# Sheet1.net
KiCad netlist of a schematic drawn in Altium Designer
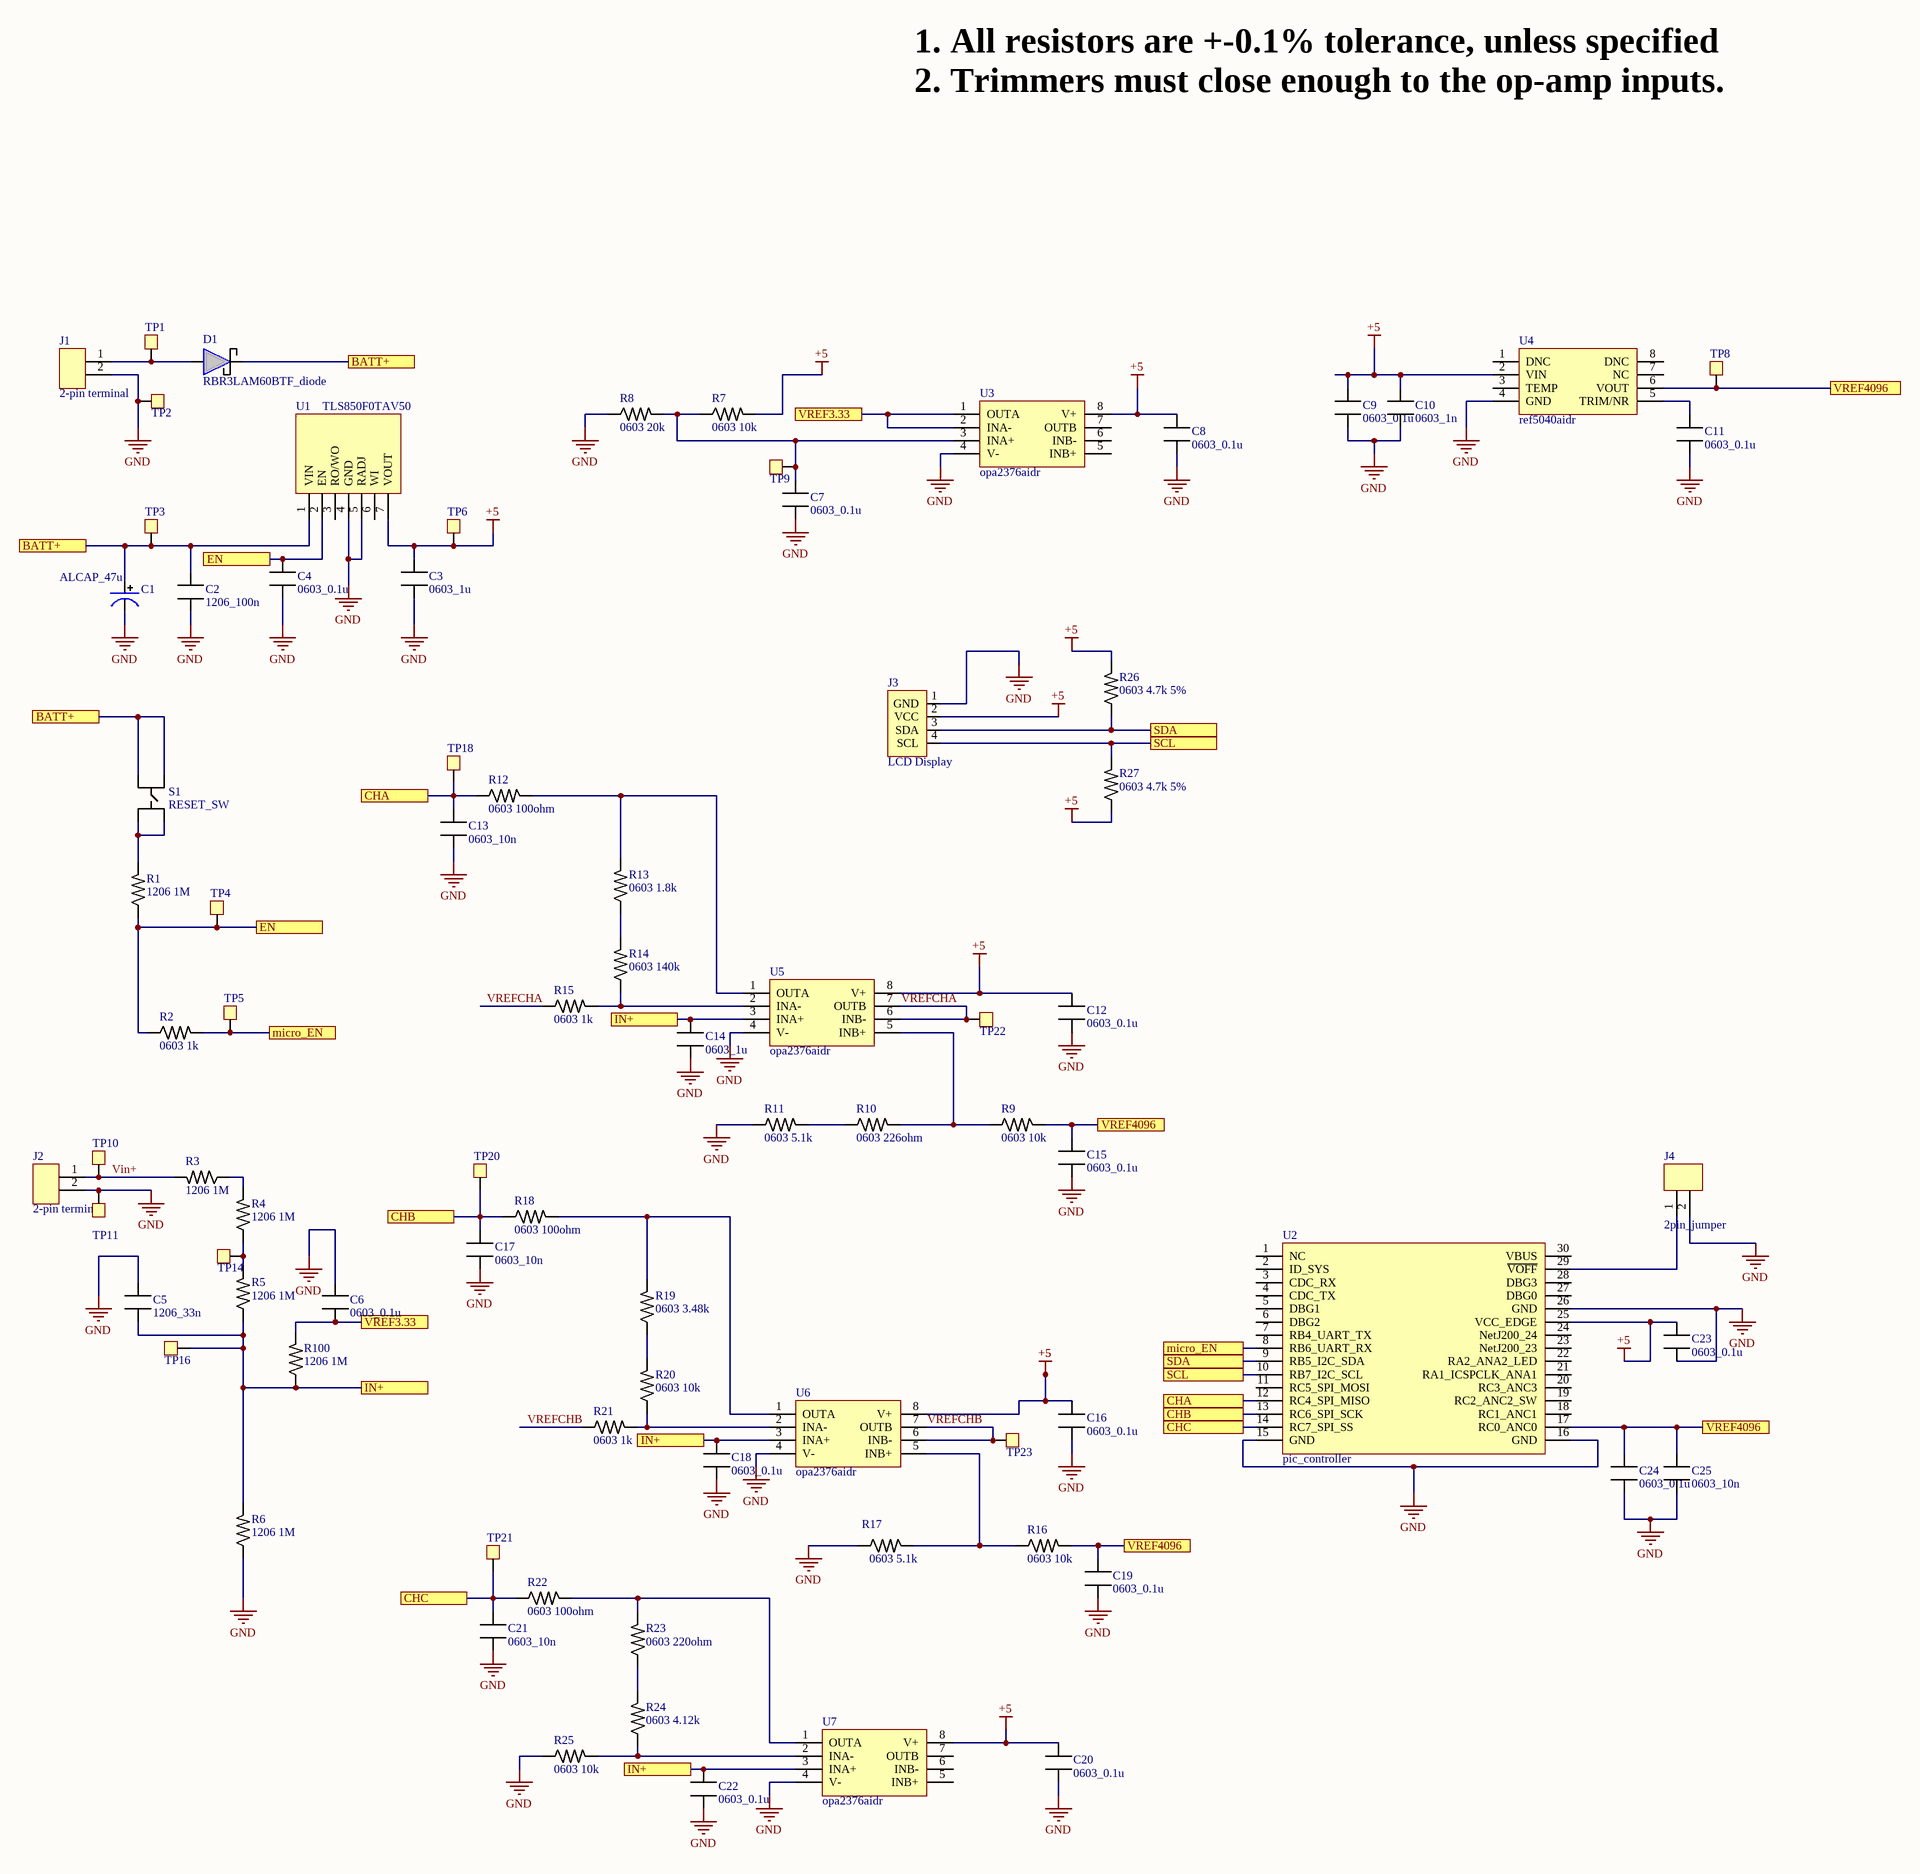
[diagram p0: Sheet1.SchDoc]

(export (version "E")
  (design (tool "Eeschema 10.0.6"))
  (components
    (comp (ref "C1")
      (value "ALCAP_47u")
      (footprint "47u_cap")
      (description "ALCAP")
      (libsource (lib "finallib") (part "ALCAP_47UF"))
    )
    (comp (ref "C2")
      (value "1206_100n")
      (footprint "CAPC3216X10M")
      (description "CAP_1206")
      (libsource (lib "finallib") (part "CAP_1206"))
    )
    (comp (ref "C3")
      (value "0603_1u")
      (footprint "CAP_0603")
      (description "CAP_0603")
      (libsource (lib "finallib") (part "CAP_0603"))
    )
    (comp (ref "C4")
      (value "0603_0.1u")
      (footprint "CAP_0603")
      (description "CAP_0603")
      (libsource (lib "finallib") (part "CAP_0603"))
    )
    (comp (ref "C5")
      (value "1206_33n")
      (footprint "CAPC3216X10M")
      (description "CAP_1206")
      (libsource (lib "finallib") (part "CAP_1206"))
    )
    (comp (ref "C6")
      (value "0603_0.1u")
      (footprint "CAP_0603")
      (description "CAP_0603")
      (libsource (lib "finallib") (part "CAP_0603"))
    )
    (comp (ref "C7")
      (value "0603_0.1u")
      (footprint "CAP_0603")
      (description "CAP_0603")
      (libsource (lib "finallib") (part "CAP_0603"))
    )
    (comp (ref "C8")
      (value "0603_0.1u")
      (footprint "CAP_0603")
      (description "CAP_0603")
      (libsource (lib "finallib") (part "CAP_0603"))
    )
    (comp (ref "C9")
      (value "0603_0.1u")
      (footprint "CAP_0603")
      (description "CAP_0603")
      (libsource (lib "finallib") (part "CAP_0603"))
    )
    (comp (ref "C10")
      (value "0603_1n")
      (footprint "CAP_0603")
      (description "CAP_0603")
      (libsource (lib "finallib") (part "CAP_0603"))
    )
    (comp (ref "C11")
      (value "0603_0.1u")
      (footprint "CAP_0603")
      (description "CAP_0603")
      (libsource (lib "finallib") (part "CAP_0603"))
    )
    (comp (ref "C12")
      (value "0603_0.1u")
      (footprint "CAP_0603")
      (description "CAP_0603")
      (libsource (lib "finallib") (part "CAP_0603"))
    )
    (comp (ref "C13")
      (value "0603_10n")
      (footprint "CAP_0603")
      (description "CAP_0603")
      (libsource (lib "finallib") (part "CAP_0603"))
    )
    (comp (ref "C14")
      (value "0603_1u")
      (footprint "CAP_0603")
      (description "CAP_0603")
      (libsource (lib "finallib") (part "CAP_0603"))
    )
    (comp (ref "C15")
      (value "0603_0.1u")
      (footprint "CAP_0603")
      (description "CAP_0603")
      (libsource (lib "finallib") (part "CAP_0603"))
    )
    (comp (ref "C16")
      (value "0603_0.1u")
      (footprint "CAP_0603")
      (description "CAP_0603")
      (libsource (lib "finallib") (part "CAP_0603"))
    )
    (comp (ref "C17")
      (value "0603_10n")
      (footprint "CAP_0603")
      (description "CAP_0603")
      (libsource (lib "finallib") (part "CAP_0603"))
    )
    (comp (ref "C18")
      (value "0603_0.1u")
      (footprint "CAP_0603")
      (description "CAP_0603")
      (libsource (lib "finallib") (part "CAP_0603"))
    )
    (comp (ref "C19")
      (value "0603_0.1u")
      (footprint "CAP_0603")
      (description "CAP_0603")
      (libsource (lib "finallib") (part "CAP_0603"))
    )
    (comp (ref "C20")
      (value "0603_0.1u")
      (footprint "CAP_0603")
      (description "CAP_0603")
      (libsource (lib "finallib") (part "CAP_0603"))
    )
    (comp (ref "C21")
      (value "0603_10n")
      (footprint "CAP_0603")
      (description "CAP_0603")
      (libsource (lib "finallib") (part "CAP_0603"))
    )
    (comp (ref "C22")
      (value "0603_0.1u")
      (footprint "CAP_0603")
      (description "CAP_0603")
      (libsource (lib "finallib") (part "CAP_0603"))
    )
    (comp (ref "C23")
      (value "0603_0.1u")
      (footprint "CAP_0603")
      (description "CAP_0603")
      (libsource (lib "finallib") (part "CAP_0603"))
    )
    (comp (ref "C24")
      (value "0603_0.1u")
      (footprint "CAP_0603")
      (description "CAP_0603")
      (libsource (lib "finallib") (part "CAP_0603"))
    )
    (comp (ref "C25")
      (value "0603_10n")
      (footprint "CAP_0603")
      (description "CAP_0603")
      (libsource (lib "finallib") (part "CAP_0603"))
    )
    (comp (ref "D1")
      (value "RBR3LAM60BTF_diode")
      (footprint "RBR3LAM60BTF_diode")
      (libsource (lib "finallib") (part "RBR3LAM60BTF_diode"))
    )
    (comp (ref "J1")
      (value "2-pin terminal")
      (footprint "2-pin terminal")
      (libsource (lib "finallib") (part "2-pin terminal"))
    )
    (comp (ref "J2")
      (value "2-pin terminal")
      (footprint "2-pin terminal")
      (libsource (lib "finallib") (part "2-pin terminal"))
    )
    (comp (ref "J3")
      (value "LCD Display")
      (footprint "LCD Display")
      (libsource (lib "finallib") (part "LCD Display"))
    )
    (comp (ref "J4")
      (value "2pin_jumper")
      (footprint "2pin_jumper")
      (libsource (lib "finallib") (part "2pin_jumper"))
    )
    (comp (ref "R1")
      (value "1206 1M")
      (footprint "RESC3216X10M")
      (description "RES_0603 1/8 W")
      (libsource (lib "finallib") (part "RES_0603"))
    )
    (comp (ref "R2")
      (value "0603 1k")
      (footprint "RES_0603")
      (description "RES_0603 1/8 W")
      (libsource (lib "finallib") (part "RES_0603"))
    )
    (comp (ref "R3")
      (value "1206 1M")
      (footprint "RESC3216X10M")
      (libsource (lib "finallib") (part "RES_1206"))
    )
    (comp (ref "R4")
      (value "1206 1M")
      (footprint "RESC3216X10M")
      (libsource (lib "finallib") (part "RES_1206"))
    )
    (comp (ref "R5")
      (value "1206 1M")
      (footprint "RESC3216X10M")
      (libsource (lib "finallib") (part "RES_1206"))
    )
    (comp (ref "R6")
      (value "1206 1M")
      (footprint "RESC3216X10M")
      (libsource (lib "finallib") (part "RES_1206"))
    )
    (comp (ref "R7")
      (value "0603 10k")
      (footprint "RES_0603")
      (description "RES_0603 1/8 W")
      (libsource (lib "finallib") (part "RES_0603"))
    )
    (comp (ref "R8")
      (value "0603 20k")
      (footprint "RES_0603")
      (description "RES_0603 1/8 W")
      (libsource (lib "finallib") (part "RES_0603"))
    )
    (comp (ref "R9")
      (value "0603 10k")
      (footprint "RES_0603")
      (description "RES_0603 1/8 W")
      (libsource (lib "finallib") (part "RES_0603"))
    )
    (comp (ref "R10")
      (value "0603 226ohm")
      (footprint "RES_0603")
      (description "RES_0603 1/8 W")
      (libsource (lib "finallib") (part "RES_0603"))
    )
    (comp (ref "R11")
      (value "0603 5.1k")
      (footprint "RES_0603")
      (description "RES_0603 1/8 W")
      (libsource (lib "finallib") (part "RES_0603"))
    )
    (comp (ref "R12")
      (value "0603 100ohm")
      (footprint "RES_0603")
      (description "RES_0603 1/8 W")
      (libsource (lib "finallib") (part "RES_0603"))
    )
    (comp (ref "R13")
      (value "0603 1.8k")
      (footprint "RES_0603")
      (description "RES_0603 1/8 W")
      (libsource (lib "finallib") (part "RES_0603"))
    )
    (comp (ref "R14")
      (value "0603 140k")
      (footprint "RES_0603")
      (description "RES_0603 1/8 W")
      (libsource (lib "finallib") (part "RES_0603"))
    )
    (comp (ref "R15")
      (value "0603 1k")
      (footprint "RES_0603")
      (description "RES_0603 1/8 W")
      (libsource (lib "finallib") (part "RES_0603"))
    )
    (comp (ref "R16")
      (value "0603 10k")
      (footprint "RES_0603")
      (description "RES_0603 1/8 W")
      (libsource (lib "finallib") (part "RES_0603"))
    )
    (comp (ref "R17")
      (value "0603 5.1k")
      (footprint "RES_0603")
      (description "RES_0603 1/8 W")
      (libsource (lib "finallib") (part "RES_0603"))
    )
    (comp (ref "R18")
      (value "0603 100ohm")
      (footprint "RES_0603")
      (description "RES_0603 1/8 W")
      (libsource (lib "finallib") (part "RES_0603"))
    )
    (comp (ref "R19")
      (value "0603 3.48k")
      (footprint "RES_0603")
      (description "RES_0603 1/8 W")
      (libsource (lib "finallib") (part "RES_0603"))
    )
    (comp (ref "R20")
      (value "0603 10k")
      (footprint "RES_0603")
      (description "RES_0603 1/8 W")
      (libsource (lib "finallib") (part "RES_0603"))
    )
    (comp (ref "R21")
      (value "0603 1k")
      (footprint "RES_0603")
      (description "RES_0603 1/8 W")
      (libsource (lib "finallib") (part "RES_0603"))
    )
    (comp (ref "R22")
      (value "0603 100ohm")
      (footprint "RES_0603")
      (description "RES_0603 1/8 W")
      (libsource (lib "finallib") (part "RES_0603"))
    )
    (comp (ref "R23")
      (value "0603 220ohm")
      (footprint "RES_0603")
      (description "RES_0603 1/8 W")
      (libsource (lib "finallib") (part "RES_0603"))
    )
    (comp (ref "R24")
      (value "0603 4.12k")
      (footprint "RES_0603")
      (description "RES_0603 1/8 W")
      (libsource (lib "finallib") (part "RES_0603"))
    )
    (comp (ref "R25")
      (value "0603 10k")
      (footprint "RES_0603")
      (description "RES_0603 1/8 W")
      (libsource (lib "finallib") (part "RES_0603"))
    )
    (comp (ref "R26")
      (value "0603 4.7k 5%")
      (footprint "RES_0603")
      (description "RES_0603 1/8 W")
      (libsource (lib "finallib") (part "RES_0603"))
    )
    (comp (ref "R27")
      (value "0603 4.7k 5%")
      (footprint "RES_0603")
      (description "RES_0603 1/8 W")
      (libsource (lib "finallib") (part "RES_0603"))
    )
    (comp (ref "R100")
      (value "1206 1M")
      (footprint "RESC3216X10M")
      (libsource (lib "finallib") (part "RES_1206"))
    )
    (comp (ref "S1") (value "RESET_SW") (footprint "RST_SW") (libsource (lib "finallib") (part "RESET_SW")))
    (comp (ref "TP1") (value "TP") (footprint "TP") (libsource (lib "") (part "TP_1")))
    (comp (ref "TP2") (value "TP") (footprint "TP") (libsource (lib "finallib") (part "TP")))
    (comp (ref "TP3") (value "TP") (footprint "TP") (libsource (lib "") (part "TP_1")))
    (comp (ref "TP4") (value "TP") (footprint "TP") (libsource (lib "") (part "TP_1")))
    (comp (ref "TP5") (value "TP") (footprint "TP") (libsource (lib "") (part "TP_1")))
    (comp (ref "TP6") (value "TP") (footprint "TP") (libsource (lib "") (part "TP_1")))
    (comp (ref "TP8") (value "TP") (footprint "TP") (libsource (lib "") (part "TP_1")))
    (comp (ref "TP9") (value "TP") (footprint "TP") (libsource (lib "") (part "TP_2")))
    (comp (ref "TP10") (value "TP") (footprint "TP") (libsource (lib "") (part "TP_1")))
    (comp (ref "TP11") (value "TP") (footprint "TP") (libsource (lib "") (part "TP_3")))
    (comp (ref "TP14") (value "TP") (footprint "TP") (libsource (lib "") (part "TP_2")))
    (comp (ref "TP16") (value "TP") (footprint "TP") (libsource (lib "") (part "TP_2")))
    (comp (ref "TP18") (value "TP") (footprint "TP") (libsource (lib "") (part "TP_1")))
    (comp (ref "TP20") (value "TP") (footprint "TP") (libsource (lib "") (part "TP_1")))
    (comp (ref "TP21") (value "TP") (footprint "TP") (libsource (lib "") (part "TP_1")))
    (comp (ref "TP22") (value "TP") (footprint "TP") (libsource (lib "finallib") (part "TP")))
    (comp (ref "TP23") (value "TP") (footprint "TP") (libsource (lib "finallib") (part "TP")))
    (comp (ref "U1")
      (value "TLS850F0TAV50")
      (footprint "TLS850F0TAV50")
      (libsource (lib "finallib") (part "TLS850F0TAV50"))
    )
    (comp (ref "U2")
      (value "pic_controller")
      (footprint "nano")
      (libsource (lib "finallib") (part "pic_controller"))
    )
    (comp (ref "U3")
      (value "opa2376aidr")
      (footprint "opa2376aidr")
      (libsource (lib "finallib") (part "opa2376aidr"))
    )
    (comp (ref "U4")
      (value "ref5040aidr")
      (footprint "ref5040aidr")
      (libsource (lib "finallib") (part "ref5040aidr"))
    )
    (comp (ref "U5")
      (value "opa2376aidr")
      (footprint "opa2376aidr")
      (libsource (lib "finallib") (part "opa2376aidr"))
    )
    (comp (ref "U6")
      (value "opa2376aidr")
      (footprint "opa2376aidr")
      (libsource (lib "finallib") (part "opa2376aidr"))
    )
    (comp (ref "U7")
      (value "opa2376aidr")
      (footprint "opa2376aidr")
      (libsource (lib "finallib") (part "opa2376aidr"))
    )
  )
  (nets
    (net (code "1") (name "+5") (class "Default")
      (node (ref "C10") (pin "2") (pinfunction "2_2") (pintype "passive"))
      (node (ref "C12") (pin "2") (pinfunction "2_2") (pintype "passive"))
      (node (ref "C16") (pin "2") (pinfunction "2_2") (pintype "passive"))
      (node (ref "C20") (pin "2") (pinfunction "2_2") (pintype "passive"))
      (node (ref "C23") (pin "1") (pinfunction "1_1") (pintype "passive"))
      (node (ref "C3") (pin "2") (pinfunction "2_2") (pintype "passive"))
      (node (ref "C8") (pin "2") (pinfunction "2_2") (pintype "passive"))
      (node (ref "C9") (pin "2") (pinfunction "2_2") (pintype "passive"))
      (node (ref "J3") (pin "2") (pinfunction "VCC_2") (pintype "passive"))
      (node (ref "R26") (pin "2") (pinfunction "2_2") (pintype "passive"))
      (node (ref "R27") (pin "1") (pinfunction "1_1") (pintype "passive"))
      (node (ref "R7") (pin "2") (pinfunction "2_2") (pintype "passive"))
      (node (ref "TP6") (pin "1") (pinfunction "1_1") (pintype "passive"))
      (node (ref "U1") (pin "7") (pinfunction "VOUT_7") (pintype "passive"))
      (node (ref "U2") (pin "25") (pinfunction "VCC_EDGE_25") (pintype "passive"))
      (node (ref "U3") (pin "8") (pinfunction "V+_8") (pintype "passive"))
      (node (ref "U4") (pin "2") (pinfunction "VIN_2") (pintype "passive"))
      (node (ref "U5") (pin "8") (pinfunction "V+_8") (pintype "passive"))
      (node (ref "U6") (pin "8") (pinfunction "V+_8") (pintype "passive"))
      (node (ref "U7") (pin "8") (pinfunction "V+_8") (pintype "passive"))
    )
    (net (code "2") (name "/BATT+") (class "Default")
      (node (ref "C1") (pin "1") (pinfunction "1_1") (pintype "passive"))
      (node (ref "C2") (pin "2") (pinfunction "2_2") (pintype "passive"))
      (node (ref "D1") (pin "1") (pinfunction "1_1") (pintype "passive"))
      (node (ref "S1") (pin "1") (pinfunction "1_1") (pintype "passive"))
      (node (ref "S1") (pin "2") (pinfunction "2_2") (pintype "passive"))
      (node (ref "TP3") (pin "1") (pinfunction "1_1") (pintype "passive"))
      (node (ref "U1") (pin "1") (pinfunction "VIN_1") (pintype "passive"))
    )
    (net (code "3") (name "/CHA") (class "Default")
      (node (ref "C13") (pin "2") (pinfunction "2_2") (pintype "passive"))
      (node (ref "R12") (pin "1") (pinfunction "1_1") (pintype "passive"))
      (node (ref "TP18") (pin "1") (pinfunction "1_1") (pintype "passive"))
      (node (ref "U2") (pin "12") (pinfunction "RC4_SPI_MISO_12") (pintype "passive"))
    )
    (net (code "4") (name "/CHB") (class "Default")
      (node (ref "C17") (pin "2") (pinfunction "2_2") (pintype "passive"))
      (node (ref "R18") (pin "1") (pinfunction "1_1") (pintype "passive"))
      (node (ref "TP20") (pin "1") (pinfunction "1_1") (pintype "passive"))
      (node (ref "U2") (pin "13") (pinfunction "RC6_SPI_SCK_13") (pintype "passive"))
    )
    (net (code "5") (name "/CHC") (class "Default")
      (node (ref "C21") (pin "2") (pinfunction "2_2") (pintype "passive"))
      (node (ref "R22") (pin "1") (pinfunction "1_1") (pintype "passive"))
      (node (ref "TP21") (pin "1") (pinfunction "1_1") (pintype "passive"))
      (node (ref "U2") (pin "14") (pinfunction "RC7_SPI_SS_14") (pintype "passive"))
    )
    (net (code "6") (name "/EN") (class "Default")
      (node (ref "C4") (pin "2") (pinfunction "2_2") (pintype "passive"))
      (node (ref "R1") (pin "1") (pinfunction "1_1") (pintype "passive"))
      (node (ref "R2") (pin "1") (pinfunction "1_1") (pintype "passive"))
      (node (ref "TP4") (pin "1") (pinfunction "1_1") (pintype "passive"))
      (node (ref "U1") (pin "2") (pinfunction "EN_2") (pintype "passive"))
    )
    (net (code "7") (name "/IN+") (class "Default")
      (node (ref "C14") (pin "2") (pinfunction "2_2") (pintype "passive"))
      (node (ref "C18") (pin "2") (pinfunction "2_2") (pintype "passive"))
      (node (ref "C22") (pin "2") (pinfunction "2_2") (pintype "passive"))
      (node (ref "C5") (pin "1") (pinfunction "1_1") (pintype "passive"))
      (node (ref "R100") (pin "1") (pinfunction "1_1") (pintype "passive"))
      (node (ref "R5") (pin "1") (pinfunction "1_1") (pintype "passive"))
      (node (ref "R6") (pin "2") (pinfunction "2_2") (pintype "passive"))
      (node (ref "TP16") (pin "1") (pinfunction "1_1") (pintype "passive"))
      (node (ref "U5") (pin "3") (pinfunction "INA+_3") (pintype "passive"))
      (node (ref "U6") (pin "3") (pinfunction "INA+_3") (pintype "passive"))
      (node (ref "U7") (pin "3") (pinfunction "INA+_3") (pintype "passive"))
    )
    (net (code "8") (name "/SCL") (class "Default")
      (node (ref "J3") (pin "4") (pinfunction "SCL_4") (pintype "passive"))
      (node (ref "R27") (pin "2") (pinfunction "2_2") (pintype "passive"))
      (node (ref "U2") (pin "10") (pinfunction "RB7_I2C_SCL_10") (pintype "passive"))
    )
    (net (code "9") (name "/SDA") (class "Default")
      (node (ref "J3") (pin "3") (pinfunction "SDA_3") (pintype "passive"))
      (node (ref "R26") (pin "1") (pinfunction "1_1") (pintype "passive"))
      (node (ref "U2") (pin "9") (pinfunction "RB5_I2C_SDA_9") (pintype "passive"))
    )
    (net (code "10") (name "/VREF3.33") (class "Default")
      (node (ref "C6") (pin "1") (pinfunction "1_1") (pintype "passive"))
      (node (ref "R100") (pin "2") (pinfunction "2_2") (pintype "passive"))
      (node (ref "U3") (pin "1") (pinfunction "OUTA_1") (pintype "passive"))
      (node (ref "U3") (pin "2") (pinfunction "INA-_2") (pintype "passive"))
    )
    (net (code "11") (name "/VREF4096") (class "Default")
      (node (ref "C15") (pin "2") (pinfunction "2_2") (pintype "passive"))
      (node (ref "C19") (pin "2") (pinfunction "2_2") (pintype "passive"))
      (node (ref "C24") (pin "1") (pinfunction "1_1") (pintype "passive"))
      (node (ref "C25") (pin "1") (pinfunction "1_1") (pintype "passive"))
      (node (ref "R16") (pin "2") (pinfunction "2_2") (pintype "passive"))
      (node (ref "R9") (pin "2") (pinfunction "2_2") (pintype "passive"))
      (node (ref "TP8") (pin "1") (pinfunction "1_1") (pintype "passive"))
      (node (ref "U2") (pin "17") (pinfunction "RC0_ANC0_17") (pintype "passive"))
      (node (ref "U4") (pin "6") (pinfunction "VOUT_6") (pintype "passive"))
    )
    (net (code "12") (name "/VREFCHA") (class "Default")
      (node (ref "R15") (pin "1") (pinfunction "1_1") (pintype "passive"))
      (node (ref "TP22") (pin "1") (pinfunction "1_1") (pintype "passive"))
      (node (ref "U5") (pin "6") (pinfunction "INB-_6") (pintype "passive"))
      (node (ref "U5") (pin "7") (pinfunction "OUTB_7") (pintype "passive"))
    )
    (net (code "13") (name "/VREFCHB") (class "Default")
      (node (ref "R21") (pin "1") (pinfunction "1_1") (pintype "passive"))
      (node (ref "TP23") (pin "1") (pinfunction "1_1") (pintype "passive"))
      (node (ref "U6") (pin "6") (pinfunction "INB-_6") (pintype "passive"))
      (node (ref "U6") (pin "7") (pinfunction "OUTB_7") (pintype "passive"))
    )
    (net (code "14") (name "/Vin+") (class "Default")
      (node (ref "J2") (pin "1") (pinfunction "1_1") (pintype "passive"))
      (node (ref "R3") (pin "2") (pinfunction "2_2") (pintype "passive"))
      (node (ref "TP10") (pin "1") (pinfunction "1_1") (pintype "passive"))
    )
    (net (code "15") (name "/micro_EN") (class "Default")
      (node (ref "R2") (pin "2") (pinfunction "2_2") (pintype "passive"))
      (node (ref "TP5") (pin "1") (pinfunction "1_1") (pintype "passive"))
      (node (ref "U2") (pin "8") (pinfunction "RB6_UART_RX_8") (pintype "passive"))
    )
    (net (code "16") (name "GND") (class "Default")
      (node (ref "C1") (pin "2") (pinfunction "2_2") (pintype "passive"))
      (node (ref "C10") (pin "1") (pinfunction "1_1") (pintype "passive"))
      (node (ref "C11") (pin "1") (pinfunction "1_1") (pintype "passive"))
      (node (ref "C12") (pin "1") (pinfunction "1_1") (pintype "passive"))
      (node (ref "C13") (pin "1") (pinfunction "1_1") (pintype "passive"))
      (node (ref "C14") (pin "1") (pinfunction "1_1") (pintype "passive"))
      (node (ref "C15") (pin "1") (pinfunction "1_1") (pintype "passive"))
      (node (ref "C16") (pin "1") (pinfunction "1_1") (pintype "passive"))
      (node (ref "C17") (pin "1") (pinfunction "1_1") (pintype "passive"))
      (node (ref "C18") (pin "1") (pinfunction "1_1") (pintype "passive"))
      (node (ref "C19") (pin "1") (pinfunction "1_1") (pintype "passive"))
      (node (ref "C2") (pin "1") (pinfunction "1_1") (pintype "passive"))
      (node (ref "C20") (pin "1") (pinfunction "1_1") (pintype "passive"))
      (node (ref "C21") (pin "1") (pinfunction "1_1") (pintype "passive"))
      (node (ref "C22") (pin "1") (pinfunction "1_1") (pintype "passive"))
      (node (ref "C23") (pin "2") (pinfunction "2_2") (pintype "passive"))
      (node (ref "C24") (pin "2") (pinfunction "2_2") (pintype "passive"))
      (node (ref "C25") (pin "2") (pinfunction "2_2") (pintype "passive"))
      (node (ref "C3") (pin "1") (pinfunction "1_1") (pintype "passive"))
      (node (ref "C4") (pin "1") (pinfunction "1_1") (pintype "passive"))
      (node (ref "C5") (pin "2") (pinfunction "2_2") (pintype "passive"))
      (node (ref "C6") (pin "2") (pinfunction "2_2") (pintype "passive"))
      (node (ref "C7") (pin "1") (pinfunction "1_1") (pintype "passive"))
      (node (ref "C8") (pin "1") (pinfunction "1_1") (pintype "passive"))
      (node (ref "C9") (pin "1") (pinfunction "1_1") (pintype "passive"))
      (node (ref "J1") (pin "2") (pinfunction "2_2") (pintype "passive"))
      (node (ref "J2") (pin "2") (pinfunction "2_2") (pintype "passive"))
      (node (ref "J3") (pin "1") (pinfunction "GND_1") (pintype "passive"))
      (node (ref "J4") (pin "2") (pinfunction "2_2") (pintype "passive"))
      (node (ref "R11") (pin "1") (pinfunction "1_1") (pintype "passive"))
      (node (ref "R17") (pin "1") (pinfunction "1_1") (pintype "passive"))
      (node (ref "R25") (pin "1") (pinfunction "1_1") (pintype "passive"))
      (node (ref "R6") (pin "1") (pinfunction "1_1") (pintype "passive"))
      (node (ref "R8") (pin "1") (pinfunction "1_1") (pintype "passive"))
      (node (ref "TP11") (pin "1") (pinfunction "1_1") (pintype "passive"))
      (node (ref "TP2") (pin "1") (pinfunction "1_1") (pintype "passive"))
      (node (ref "U1") (pin "4") (pinfunction "GND_4") (pintype "passive"))
      (node (ref "U1") (pin "5") (pinfunction "RADJ_5") (pintype "passive"))
      (node (ref "U2") (pin "15") (pinfunction "GND_15") (pintype "passive"))
      (node (ref "U2") (pin "16") (pinfunction "GND_16") (pintype "passive"))
      (node (ref "U2") (pin "26") (pinfunction "GND_26") (pintype "passive"))
      (node (ref "U3") (pin "4") (pinfunction "V-_4") (pintype "passive"))
      (node (ref "U4") (pin "4") (pinfunction "GND_4") (pintype "passive"))
      (node (ref "U5") (pin "4") (pinfunction "V-_4") (pintype "passive"))
      (node (ref "U6") (pin "4") (pinfunction "V-_4") (pintype "passive"))
      (node (ref "U7") (pin "4") (pinfunction "V-_4") (pintype "passive"))
    )
    (net (code "17") (name "Net-(D1-Pad2)") (class "Default")
      (node (ref "D1") (pin "2") (pinfunction "2_2") (pintype "passive"))
      (node (ref "J1") (pin "1") (pinfunction "1_1") (pintype "passive"))
      (node (ref "TP1") (pin "1") (pinfunction "1_1") (pintype "passive"))
    )
    (net (code "18") (name "Net-(R1-Pad2)") (class "Default")
      (node (ref "R1") (pin "2") (pinfunction "2_2") (pintype "passive"))
      (node (ref "S1") (pin "3") (pinfunction "3_3") (pintype "passive"))
      (node (ref "S1") (pin "4") (pinfunction "4_4") (pintype "passive"))
    )
    (net (code "19") (name "Net-(R3-Pad1)") (class "Default")
      (node (ref "R3") (pin "1") (pinfunction "1_1") (pintype "passive"))
      (node (ref "R4") (pin "2") (pinfunction "2_2") (pintype "passive"))
    )
    (net (code "20") (name "Net-(R4-Pad1)") (class "Default")
      (node (ref "R4") (pin "1") (pinfunction "1_1") (pintype "passive"))
      (node (ref "R5") (pin "2") (pinfunction "2_2") (pintype "passive"))
      (node (ref "TP14") (pin "1") (pinfunction "1_1") (pintype "passive"))
    )
    (net (code "21") (name "Net-(R10-Pad1)") (class "Default")
      (node (ref "R10") (pin "1") (pinfunction "1_1") (pintype "passive"))
      (node (ref "R11") (pin "2") (pinfunction "2_2") (pintype "passive"))
    )
    (net (code "22") (name "Net-(R13-Pad1)") (class "Default")
      (node (ref "R13") (pin "1") (pinfunction "1_1") (pintype "passive"))
      (node (ref "R14") (pin "2") (pinfunction "2_2") (pintype "passive"))
    )
    (net (code "23") (name "Net-(R19-Pad1)") (class "Default")
      (node (ref "R19") (pin "1") (pinfunction "1_1") (pintype "passive"))
      (node (ref "R20") (pin "2") (pinfunction "2_2") (pintype "passive"))
    )
    (net (code "24") (name "Net-(R23-Pad1)") (class "Default")
      (node (ref "R23") (pin "1") (pinfunction "1_1") (pintype "passive"))
      (node (ref "R24") (pin "2") (pinfunction "2_2") (pintype "passive"))
    )
    (net (code "25") (name "Net-(U2-~{VOFF})") (class "Default")
      (node (ref "J4") (pin "1") (pinfunction "1_1") (pintype "passive"))
      (node (ref "U2") (pin "29") (pinfunction "~{VOFF}_29") (pintype "passive"))
    )
    (net (code "26") (name "Net-(U3-INA+)") (class "Default")
      (node (ref "C7") (pin "2") (pinfunction "2_2") (pintype "passive"))
      (node (ref "R7") (pin "1") (pinfunction "1_1") (pintype "passive"))
      (node (ref "R8") (pin "2") (pinfunction "2_2") (pintype "passive"))
      (node (ref "TP9") (pin "1") (pinfunction "1_1") (pintype "passive"))
      (node (ref "U3") (pin "3") (pinfunction "INA+_3") (pintype "passive"))
    )
    (net (code "27") (name "Net-(U4-TRIM{slash}NR)") (class "Default")
      (node (ref "C11") (pin "2") (pinfunction "2_2") (pintype "passive"))
      (node (ref "U4") (pin "5") (pinfunction "TRIM/NR_5") (pintype "passive"))
    )
    (net (code "28") (name "Net-(U5-INA-)") (class "Default")
      (node (ref "R14") (pin "1") (pinfunction "1_1") (pintype "passive"))
      (node (ref "R15") (pin "2") (pinfunction "2_2") (pintype "passive"))
      (node (ref "U5") (pin "2") (pinfunction "INA-_2") (pintype "passive"))
    )
    (net (code "29") (name "Net-(U5-INB+)") (class "Default")
      (node (ref "R10") (pin "2") (pinfunction "2_2") (pintype "passive"))
      (node (ref "R9") (pin "1") (pinfunction "1_1") (pintype "passive"))
      (node (ref "U5") (pin "5") (pinfunction "INB+_5") (pintype "passive"))
    )
    (net (code "30") (name "Net-(U5-OUTA)") (class "Default")
      (node (ref "R12") (pin "2") (pinfunction "2_2") (pintype "passive"))
      (node (ref "R13") (pin "2") (pinfunction "2_2") (pintype "passive"))
      (node (ref "U5") (pin "1") (pinfunction "OUTA_1") (pintype "passive"))
    )
    (net (code "31") (name "Net-(U6-INA-)") (class "Default")
      (node (ref "R20") (pin "1") (pinfunction "1_1") (pintype "passive"))
      (node (ref "R21") (pin "2") (pinfunction "2_2") (pintype "passive"))
      (node (ref "U6") (pin "2") (pinfunction "INA-_2") (pintype "passive"))
    )
    (net (code "32") (name "Net-(U6-INB+)") (class "Default")
      (node (ref "R16") (pin "1") (pinfunction "1_1") (pintype "passive"))
      (node (ref "R17") (pin "2") (pinfunction "2_2") (pintype "passive"))
      (node (ref "U6") (pin "5") (pinfunction "INB+_5") (pintype "passive"))
    )
    (net (code "33") (name "Net-(U6-OUTA)") (class "Default")
      (node (ref "R18") (pin "2") (pinfunction "2_2") (pintype "passive"))
      (node (ref "R19") (pin "2") (pinfunction "2_2") (pintype "passive"))
      (node (ref "U6") (pin "1") (pinfunction "OUTA_1") (pintype "passive"))
    )
    (net (code "34") (name "Net-(U7-INA-)") (class "Default")
      (node (ref "R24") (pin "1") (pinfunction "1_1") (pintype "passive"))
      (node (ref "R25") (pin "2") (pinfunction "2_2") (pintype "passive"))
      (node (ref "U7") (pin "2") (pinfunction "INA-_2") (pintype "passive"))
    )
    (net (code "35") (name "Net-(U7-OUTA)") (class "Default")
      (node (ref "R22") (pin "2") (pinfunction "2_2") (pintype "passive"))
      (node (ref "R23") (pin "2") (pinfunction "2_2") (pintype "passive"))
      (node (ref "U7") (pin "1") (pinfunction "OUTA_1") (pintype "passive"))
    )
    (net (code "36") (name "unconnected-(U1-RO{slash}WO-Pad3)") (class "Default")
      (node (ref "U1") (pin "3") (pinfunction "RO/WO_3") (pintype "passive"))
    )
    (net (code "37") (name "unconnected-(U1-WI-Pad6)") (class "Default")
      (node (ref "U1") (pin "6") (pinfunction "WI_6") (pintype "passive"))
    )
    (net (code "38") (name "unconnected-(U2-CDC_RX-Pad3)") (class "Default")
      (node (ref "U2") (pin "3") (pinfunction "CDC_RX_3") (pintype "passive"))
    )
    (net (code "39") (name "unconnected-(U2-CDC_TX-Pad4)") (class "Default")
      (node (ref "U2") (pin "4") (pinfunction "CDC_TX_4") (pintype "passive"))
    )
    (net (code "40") (name "unconnected-(U2-DBG0-Pad27)") (class "Default")
      (node (ref "U2") (pin "27") (pinfunction "DBG0_27") (pintype "passive"))
    )
    (net (code "41") (name "unconnected-(U2-DBG1-Pad5)") (class "Default")
      (node (ref "U2") (pin "5") (pinfunction "DBG1_5") (pintype "passive"))
    )
    (net (code "42") (name "unconnected-(U2-DBG2-Pad6)") (class "Default")
      (node (ref "U2") (pin "6") (pinfunction "DBG2_6") (pintype "passive"))
    )
    (net (code "43") (name "unconnected-(U2-DBG3-Pad28)") (class "Default")
      (node (ref "U2") (pin "28") (pinfunction "DBG3_28") (pintype "passive"))
    )
    (net (code "44") (name "unconnected-(U2-ID_SYS-Pad2)") (class "Default")
      (node (ref "U2") (pin "2") (pinfunction "ID_SYS_2") (pintype "passive"))
    )
    (net (code "45") (name "unconnected-(U2-NC-Pad1)") (class "Default")
      (node (ref "U2") (pin "1") (pinfunction "NC_1") (pintype "passive"))
    )
    (net (code "46") (name "unconnected-(U2-NetJ200_23-Pad23)") (class "Default")
      (node (ref "U2") (pin "23") (pinfunction "NetJ200_23_23") (pintype "passive"))
    )
    (net (code "47") (name "unconnected-(U2-NetJ200_24-Pad24)") (class "Default")
      (node (ref "U2") (pin "24") (pinfunction "NetJ200_24_24") (pintype "passive"))
    )
    (net (code "48") (name "unconnected-(U2-RA1_ICSPCLK_ANA1-Pad21)") (class "Default")
      (node (ref "U2") (pin "21") (pinfunction "RA1_ICSPCLK_ANA1_21") (pintype "passive"))
    )
    (net (code "49") (name "unconnected-(U2-RA2_ANA2_LED-Pad22)") (class "Default")
      (node (ref "U2") (pin "22") (pinfunction "RA2_ANA2_LED_22") (pintype "passive"))
    )
    (net (code "50") (name "unconnected-(U2-RB4_UART_TX-Pad7)") (class "Default")
      (node (ref "U2") (pin "7") (pinfunction "RB4_UART_TX_7") (pintype "passive"))
    )
    (net (code "51") (name "unconnected-(U2-RC1_ANC1-Pad18)") (class "Default")
      (node (ref "U2") (pin "18") (pinfunction "RC1_ANC1_18") (pintype "passive"))
    )
    (net (code "52") (name "unconnected-(U2-RC2_ANC2_SW-Pad19)") (class "Default")
      (node (ref "U2") (pin "19") (pinfunction "RC2_ANC2_SW_19") (pintype "passive"))
    )
    (net (code "53") (name "unconnected-(U2-RC3_ANC3-Pad20)") (class "Default")
      (node (ref "U2") (pin "20") (pinfunction "RC3_ANC3_20") (pintype "passive"))
    )
    (net (code "54") (name "unconnected-(U2-RC5_SPI_MOSI-Pad11)") (class "Default")
      (node (ref "U2") (pin "11") (pinfunction "RC5_SPI_MOSI_11") (pintype "passive"))
    )
    (net (code "55") (name "unconnected-(U2-VBUS-Pad30)") (class "Default")
      (node (ref "U2") (pin "30") (pinfunction "VBUS_30") (pintype "passive"))
    )
    (net (code "56") (name "unconnected-(U3-INB+-Pad5)") (class "Default")
      (node (ref "U3") (pin "5") (pinfunction "INB+_5") (pintype "passive"))
    )
    (net (code "57") (name "unconnected-(U3-INB--Pad6)") (class "Default")
      (node (ref "U3") (pin "6") (pinfunction "INB-_6") (pintype "passive"))
    )
    (net (code "58") (name "unconnected-(U3-OUTB-Pad7)") (class "Default")
      (node (ref "U3") (pin "7") (pinfunction "OUTB_7") (pintype "passive"))
    )
    (net (code "59") (name "unconnected-(U4-DNC-Pad1)") (class "Default")
      (node (ref "U4") (pin "1") (pinfunction "DNC_1") (pintype "passive"))
    )
    (net (code "60") (name "unconnected-(U4-DNC-Pad8)") (class "Default")
      (node (ref "U4") (pin "8") (pinfunction "DNC_8") (pintype "passive"))
    )
    (net (code "61") (name "unconnected-(U4-NC-Pad7)") (class "Default")
      (node (ref "U4") (pin "7") (pinfunction "NC_7") (pintype "passive"))
    )
    (net (code "62") (name "unconnected-(U4-TEMP-Pad3)") (class "Default")
      (node (ref "U4") (pin "3") (pinfunction "TEMP_3") (pintype "passive"))
    )
    (net (code "63") (name "unconnected-(U7-INB+-Pad5)") (class "Default")
      (node (ref "U7") (pin "5") (pinfunction "INB+_5") (pintype "passive"))
    )
    (net (code "64") (name "unconnected-(U7-INB--Pad6)") (class "Default")
      (node (ref "U7") (pin "6") (pinfunction "INB-_6") (pintype "passive"))
    )
    (net (code "65") (name "unconnected-(U7-OUTB-Pad7)") (class "Default")
      (node (ref "U7") (pin "7") (pinfunction "OUTB_7") (pintype "passive"))
    )
  )
)
